# template_attiny_44.net
KiCad netlist of a schematic drawn in EAGLE
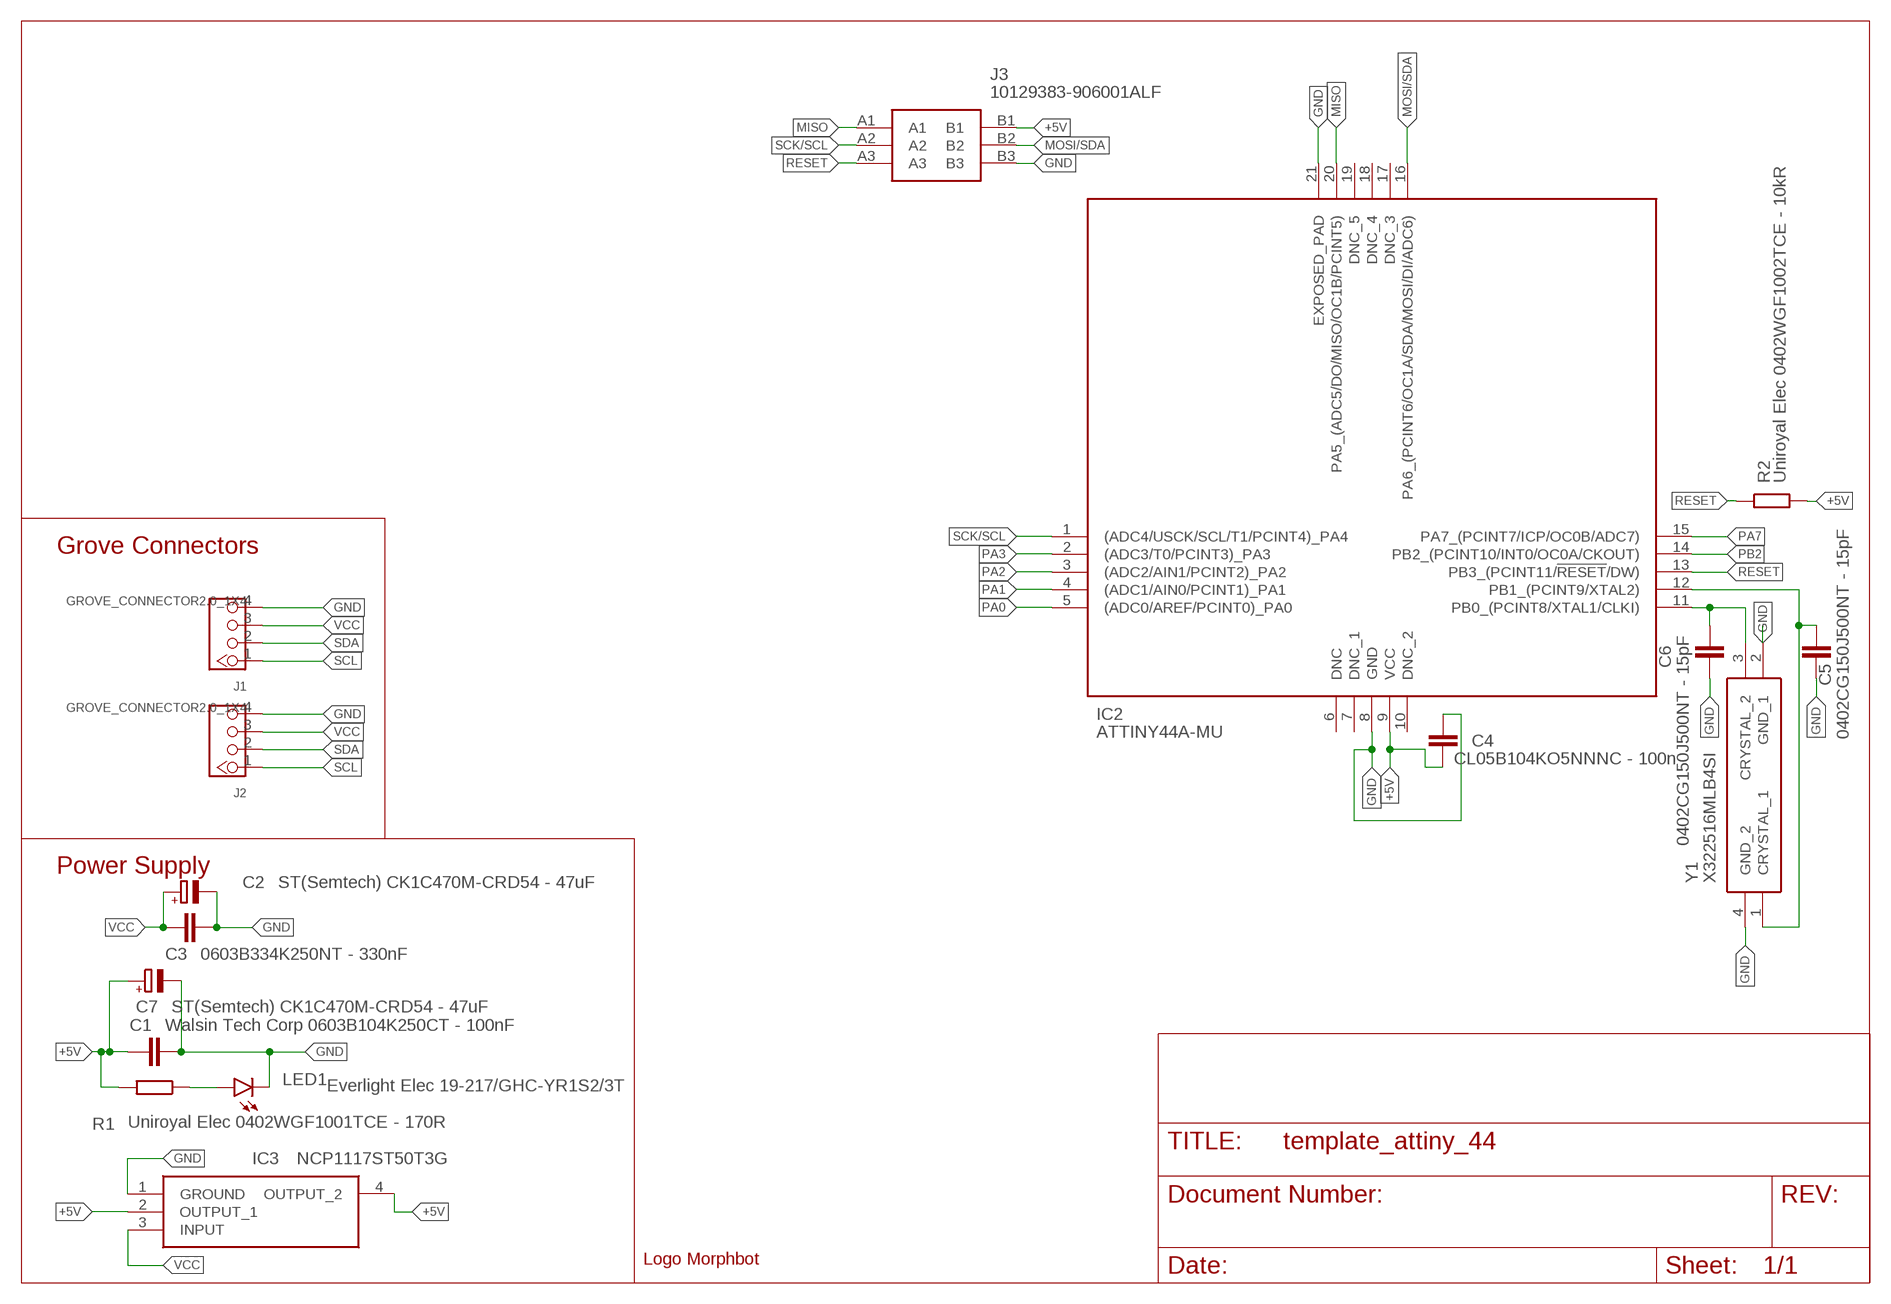
[diagram p0: schematic, sheet 1]

(export (version "E")
  (design (tool "Eeschema 10.0.6"))
  (components
    (comp (ref "C1")
      (value "Walsin Tech Corp 0603B104K250CT - 100nF")
      (footprint "eagle-import:C0603")
      (libsource (lib "eagle-import") (part "C-EUC0603"))
    )
    (comp (ref "C2")
      (value "ST(Semtech) CK1C470M-CRD54 - 47uF")
      (footprint "eagle-import:PANASONIC_C")
      (libsource (lib "eagle-import") (part "CPOL-EUC"))
    )
    (comp (ref "C3")
      (value "0603B334K250NT - 330nF")
      (footprint "eagle-import:C0603")
      (libsource (lib "eagle-import") (part "C-EUC0603"))
    )
    (comp (ref "C4")
      (value "CL05B104KO5NNNC - 100n")
      (footprint "eagle-import:C0402")
      (libsource (lib "eagle-import") (part "C-EUC0402"))
    )
    (comp (ref "C5")
      (value "0402CG150J500NT - 15pF")
      (footprint "eagle-import:C0402")
      (libsource (lib "eagle-import") (part "C-EUC0402"))
    )
    (comp (ref "C6")
      (value "0402CG150J500NT - 15pF")
      (footprint "eagle-import:C0402")
      (libsource (lib "eagle-import") (part "C-EUC0402"))
    )
    (comp (ref "C7")
      (value "ST(Semtech) CK1C470M-CRD54 - 47uF")
      (footprint "eagle-import:PANASONIC_C")
      (libsource (lib "eagle-import") (part "CPOL-EUC"))
    )
    (comp (ref "IC2")
      (value "ATTINY44A-MU")
      (footprint "eagle-import:QFN50P400X400X80-21N")
      (fields (field (name "MOUSER_PART_NUMBER") "556-ATTINY44A-MU"))
      (libsource (lib "eagle-import") (part "ATTINY44A-MU"))
    )
    (comp (ref "IC3")
      (value "NCP1117ST50T3G")
      (footprint "eagle-import:SOT230P700X180-4N")
      (fields (field (name "MOUSER_PART_NUMBER") "863-NCP1117ST50T3G"))
      (libsource (lib "eagle-import") (part "NCP1117ST50T3G"))
    )
    (comp (ref "J1")
      (value "GROVE_CONNECTOR2.0_1X4")
      (footprint "eagle-import:2.0_1X4_STRAIGHT")
      (libsource (lib "eagle-import") (part "GROVE_CONNECTOR2.0_1X4"))
    )
    (comp (ref "J2")
      (value "GROVE_CONNECTOR2.0_1X4")
      (footprint "eagle-import:2.0_1X4_STRAIGHT")
      (libsource (lib "eagle-import") (part "GROVE_CONNECTOR2.0_1X4"))
    )
    (comp (ref "J3")
      (value "10129383-906001ALF")
      (footprint "eagle-import:10129383906001ALF")
      (fields (field (name "MOUSER_PART_NUMBER") "649-1012938390601ALF"))
      (libsource (lib "eagle-import") (part "10129383-906001ALF"))
    )
    (comp (ref "LED1")
      (value "Everlight Elec 19-217/GHC-YR1S2/3T")
      (footprint "eagle-import:CHIPLED_0603")
      (libsource (lib "eagle-import") (part "LEDCHIPLED_0603"))
    )
    (comp (ref "R1")
      (value "Uniroyal Elec 0402WGF1001TCE - 170R")
      (footprint "eagle-import:R0402")
      (libsource (lib "eagle-import") (part "R-EU_R0402"))
    )
    (comp (ref "R2")
      (value "Uniroyal Elec 0402WGF1002TCE - 10kR")
      (footprint "eagle-import:R0402")
      (libsource (lib "eagle-import") (part "R-EU_R0402"))
    )
    (comp (ref "U$1")
      (value "LOGO_MORPHBOT5MM")
      (footprint "eagle-import:LOGO_MORPHBOT")
      (libsource (lib "eagle-import") (part "LOGO_MORPHBOT5MM"))
    )
    (comp (ref "Y1")
      (value "X322516MLB4SI")
      (footprint "eagle-import:X322516MLB4SI")
      (libsource (lib "eagle-import") (part "X322516MLB4SI"))
    )
  )
  (nets
    (net (code "1") (name "+5V") (class "Default")
      (node (ref "C1") (pin "1") (pinfunction "1_1") (pintype "passive"))
      (node (ref "C4") (pin "1") (pinfunction "1_1") (pintype "passive"))
      (node (ref "C7") (pin "+") (pinfunction "+_+") (pintype "passive"))
      (node (ref "IC2") (pin "9") (pinfunction "VCC_9") (pintype "power_in"))
      (node (ref "IC3") (pin "2") (pinfunction "OUTPUT_1_2") (pintype "bidirectional"))
      (node (ref "IC3") (pin "4") (pinfunction "OUTPUT_2_4") (pintype "bidirectional"))
      (node (ref "J3") (pin "B1") (pinfunction "B1_B1") (pintype "bidirectional"))
      (node (ref "R1") (pin "2") (pinfunction "2_2") (pintype "passive"))
      (node (ref "R2") (pin "2") (pinfunction "2_2") (pintype "passive"))
    )
    (net (code "2") (name "GND") (class "Default")
      (node (ref "C1") (pin "2") (pinfunction "2_2") (pintype "passive"))
      (node (ref "C2") (pin "-") (pinfunction "-_-") (pintype "passive"))
      (node (ref "C3") (pin "1") (pinfunction "1_1") (pintype "passive"))
      (node (ref "C4") (pin "2") (pinfunction "2_2") (pintype "passive"))
      (node (ref "C5") (pin "1") (pinfunction "1_1") (pintype "passive"))
      (node (ref "C6") (pin "1") (pinfunction "1_1") (pintype "passive"))
      (node (ref "C7") (pin "-") (pinfunction "-_-") (pintype "passive"))
      (node (ref "IC2") (pin "21") (pinfunction "EXPOSED_PAD_21") (pintype "bidirectional"))
      (node (ref "IC2") (pin "8") (pinfunction "GND_8") (pintype "power_in"))
      (node (ref "IC3") (pin "1") (pinfunction "GROUND_1") (pintype "bidirectional"))
      (node (ref "J1") (pin "4") (pinfunction "4_4") (pintype "bidirectional"))
      (node (ref "J2") (pin "4") (pinfunction "4_4") (pintype "bidirectional"))
      (node (ref "J3") (pin "B3") (pinfunction "B3_B3") (pintype "bidirectional"))
      (node (ref "LED1") (pin "C") (pinfunction "C_C") (pintype "passive"))
      (node (ref "Y1") (pin "2") (pinfunction "GND_1_2") (pintype "bidirectional"))
      (node (ref "Y1") (pin "4") (pinfunction "GND_2_4") (pintype "bidirectional"))
    )
    (net (code "3") (name "MISO") (class "Default")
      (node (ref "IC2") (pin "20") (pinfunction "PA5_(ADC5/DO/MISO/OC1B/PCINT5)_20") (pintype "input"))
      (node (ref "J3") (pin "A1") (pinfunction "A1_A1") (pintype "bidirectional"))
    )
    (net (code "4") (name "MOSI{slash}SDA") (class "Default")
      (node (ref "IC2") (pin "16") (pinfunction "PA6_(PCINT6/OC1A/SDA/MOSI/DI/ADC6)_16") (pintype "input"))
      (node (ref "J3") (pin "B2") (pinfunction "B2_B2") (pintype "bidirectional"))
    )
    (net (code "5") (name "Net-(IC2-PB0_(PCINT8{slash}XTAL1{slash}CLKI))") (class "Default")
      (node (ref "C6") (pin "2") (pinfunction "2_2") (pintype "passive"))
      (node (ref "IC2") (pin "11") (pinfunction "PB0_(PCINT8/XTAL1/CLKI)_11") (pintype "input"))
      (node (ref "Y1") (pin "3") (pinfunction "CRYSTAL_2_3") (pintype "bidirectional"))
    )
    (net (code "6") (name "Net-(IC2-PB1_(PCINT9{slash}XTAL2))") (class "Default")
      (node (ref "C5") (pin "2") (pinfunction "2_2") (pintype "passive"))
      (node (ref "IC2") (pin "12") (pinfunction "PB1_(PCINT9/XTAL2)_12") (pintype "input"))
      (node (ref "Y1") (pin "1") (pinfunction "CRYSTAL_1_1") (pintype "bidirectional"))
    )
    (net (code "7") (name "Net-(LED1-PadA)") (class "Default")
      (node (ref "LED1") (pin "A") (pinfunction "A_A") (pintype "passive"))
      (node (ref "R1") (pin "1") (pinfunction "1_1") (pintype "passive"))
    )
    (net (code "8") (name "PA0") (class "Default")
      (node (ref "IC2") (pin "5") (pinfunction "(ADC0/AREF/PCINT0)_PA0_5") (pintype "input"))
    )
    (net (code "9") (name "PA1") (class "Default")
      (node (ref "IC2") (pin "4") (pinfunction "(ADC1/AIN0/PCINT1)_PA1_4") (pintype "input"))
    )
    (net (code "10") (name "PA2") (class "Default")
      (node (ref "IC2") (pin "3") (pinfunction "(ADC2/AIN1/PCINT2)_PA2_3") (pintype "input"))
    )
    (net (code "11") (name "PA3") (class "Default")
      (node (ref "IC2") (pin "2") (pinfunction "(ADC3/T0/PCINT3)_PA3_2") (pintype "input"))
    )
    (net (code "12") (name "PA7") (class "Default")
      (node (ref "IC2") (pin "15") (pinfunction "PA7_(PCINT7/ICP/OC0B/ADC7)_15") (pintype "input"))
    )
    (net (code "13") (name "PB2") (class "Default")
      (node (ref "IC2") (pin "14") (pinfunction "PB2_(PCINT10/INT0/OC0A/CKOUT)_14") (pintype "output"))
    )
    (net (code "14") (name "RESET") (class "Default")
      (node (ref "IC2") (pin "13") (pinfunction "PB3_(PCINT11/~{RESET}/DW)_13") (pintype "input"))
      (node (ref "J3") (pin "A3") (pinfunction "A3_A3") (pintype "bidirectional"))
      (node (ref "R2") (pin "1") (pinfunction "1_1") (pintype "passive"))
    )
    (net (code "15") (name "SCK{slash}SCL") (class "Default")
      (node (ref "IC2") (pin "1") (pinfunction "(ADC4/USCK/SCL/T1/PCINT4)_PA4_1") (pintype "input"))
      (node (ref "J3") (pin "A2") (pinfunction "A2_A2") (pintype "bidirectional"))
    )
    (net (code "16") (name "SCL") (class "Default")
      (node (ref "J1") (pin "1") (pinfunction "1_1") (pintype "bidirectional"))
      (node (ref "J2") (pin "1") (pinfunction "1_1") (pintype "bidirectional"))
    )
    (net (code "17") (name "SDA") (class "Default")
      (node (ref "J1") (pin "2") (pinfunction "2_2") (pintype "bidirectional"))
      (node (ref "J2") (pin "2") (pinfunction "2_2") (pintype "bidirectional"))
    )
    (net (code "18") (name "VCC") (class "Default")
      (node (ref "C2") (pin "+") (pinfunction "+_+") (pintype "passive"))
      (node (ref "C3") (pin "2") (pinfunction "2_2") (pintype "passive"))
      (node (ref "IC3") (pin "3") (pinfunction "INPUT_3") (pintype "bidirectional"))
      (node (ref "J1") (pin "3") (pinfunction "3_3") (pintype "bidirectional"))
      (node (ref "J2") (pin "3") (pinfunction "3_3") (pintype "bidirectional"))
    )
    (net (code "19") (name "unconnected-(IC2-DNC-Pad6)") (class "Default")
      (node (ref "IC2") (pin "6") (pinfunction "DNC_6") (pintype "bidirectional"))
    )
    (net (code "20") (name "unconnected-(IC2-DNC_1-Pad7)") (class "Default")
      (node (ref "IC2") (pin "7") (pinfunction "DNC_1_7") (pintype "bidirectional"))
    )
    (net (code "21") (name "unconnected-(IC2-DNC_2-Pad10)") (class "Default")
      (node (ref "IC2") (pin "10") (pinfunction "DNC_2_10") (pintype "bidirectional"))
    )
    (net (code "22") (name "unconnected-(IC2-DNC_3-Pad17)") (class "Default")
      (node (ref "IC2") (pin "17") (pinfunction "DNC_3_17") (pintype "bidirectional"))
    )
    (net (code "23") (name "unconnected-(IC2-DNC_4-Pad18)") (class "Default")
      (node (ref "IC2") (pin "18") (pinfunction "DNC_4_18") (pintype "bidirectional"))
    )
    (net (code "24") (name "unconnected-(IC2-DNC_5-Pad19)") (class "Default")
      (node (ref "IC2") (pin "19") (pinfunction "DNC_5_19") (pintype "bidirectional"))
    )
  )
)
